# 1-Schematic_tiny_bloom.net
KiCad netlist of a schematic drawn in EasyEDA
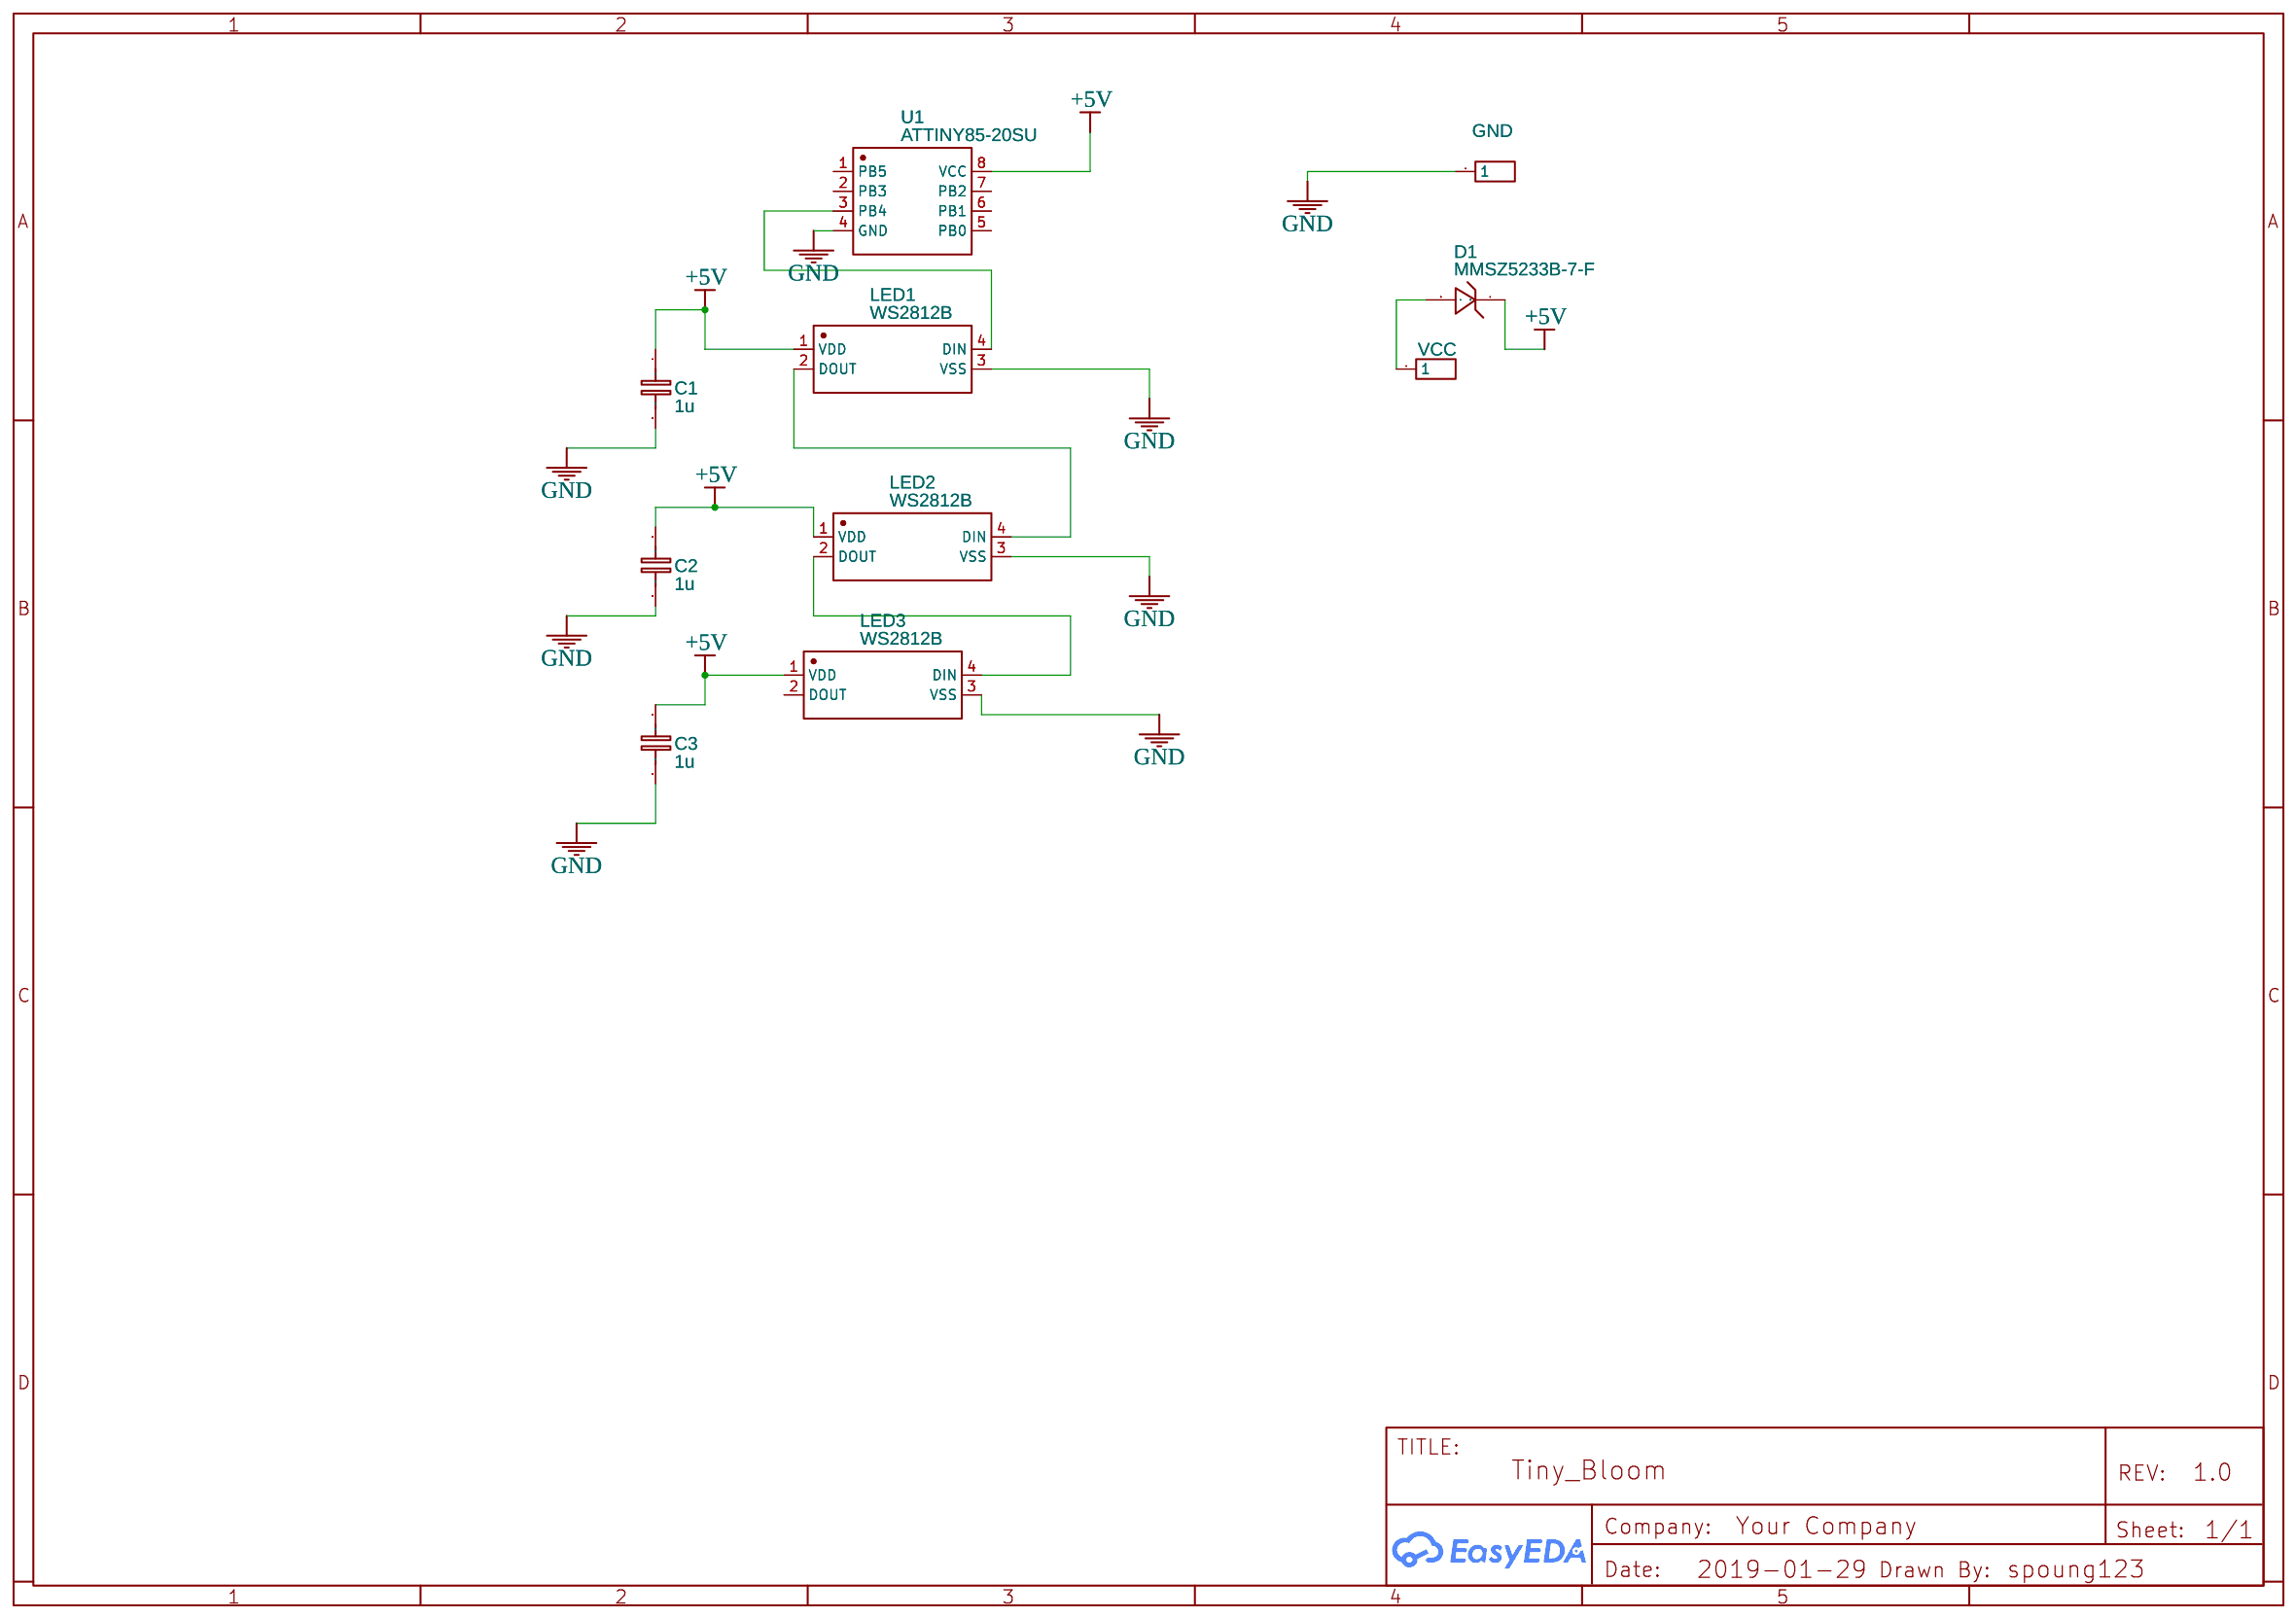
[diagram p0: schematic sheet]

(export (version "E")
  (design (tool "Eeschema 10.0.6"))
  (components
    (comp (ref "C1")
      (value "1u")
      (fields (field (name "BOM_Manufacturer Part") "?"))
      (libsource (lib "") (part "Cap_0603_EU"))
    )
    (comp (ref "C2")
      (value "1u")
      (fields (field (name "BOM_Manufacturer Part") "?"))
      (libsource (lib "") (part "Cap_0603_EU"))
    )
    (comp (ref "C3")
      (value "1u")
      (fields (field (name "BOM_Manufacturer Part") "?"))
      (libsource (lib "") (part "Cap_0603_EU"))
    )
    (comp (ref "D1")
      (value "MMSZ5233B-7-F")
      (fields (field (name "BOM_Supplier Part") "C151381"))
      (libsource (lib "") (part "Unknown_735_145"))
    )
    (comp (ref "GND")
      (value "Header-Male-2.54_1x1")
      (fields (field (name "BOM_Supplier Part") "C81276"))
      (libsource (lib "") (part "Unknown_745_80"))
    )
    (comp (ref "LED1")
      (value "WS2812B")
      (fields (field (name "BOM_Supplier Part") "C114585"))
      (libsource (lib "") (part "Unknown_445_160"))
    )
    (comp (ref "LED2")
      (value "WS2812B")
      (fields (field (name "BOM_Supplier Part") "C114585"))
      (libsource (lib "") (part "Unknown_455_255"))
    )
    (comp (ref "LED3")
      (value "WS2812B")
      (fields (field (name "BOM_Supplier Part") "C114585"))
      (libsource (lib "") (part "Unknown_440_325"))
    )
    (comp (ref "U1")
      (value "ATTINY85-20SU")
      (fields (field (name "BOM_Supplier Part") "C89852"))
      (libsource (lib "") (part "Unknown_455_95"))
    )
    (comp (ref "VCC")
      (value "Header-Male-2.54_1x1")
      (fields (field (name "BOM_Supplier Part") "C81276"))
      (libsource (lib "") (part "Unknown_715_180"))
    )
  )
  (nets
    (net (code "1") (name "+5V") (class "Default")
      (node (ref "C1") (pin "1") (pinfunction "1_1") (pintype "unspecified"))
      (node (ref "C2") (pin "1") (pinfunction "1_1") (pintype "unspecified"))
      (node (ref "C3") (pin "1") (pinfunction "1_1") (pintype "unspecified"))
      (node (ref "D1") (pin "1") (pinfunction "C_1") (pintype "unspecified"))
      (node (ref "LED1") (pin "1") (pinfunction "VDD_1") (pintype "unspecified"))
      (node (ref "LED2") (pin "1") (pinfunction "VDD_1") (pintype "unspecified"))
      (node (ref "LED3") (pin "1") (pinfunction "VDD_1") (pintype "unspecified"))
      (node (ref "U1") (pin "8") (pinfunction "VCC_8") (pintype "unspecified"))
    )
    (net (code "2") (name "GND") (class "Default")
      (node (ref "C1") (pin "2") (pinfunction "2_2") (pintype "unspecified"))
      (node (ref "C2") (pin "2") (pinfunction "2_2") (pintype "unspecified"))
      (node (ref "C3") (pin "2") (pinfunction "2_2") (pintype "unspecified"))
      (node (ref "GND") (pin "1") (pinfunction "1_1") (pintype "input"))
      (node (ref "LED1") (pin "3") (pinfunction "VSS_3") (pintype "unspecified"))
      (node (ref "LED2") (pin "3") (pinfunction "VSS_3") (pintype "unspecified"))
      (node (ref "LED3") (pin "3") (pinfunction "VSS_3") (pintype "unspecified"))
      (node (ref "U1") (pin "4") (pinfunction "GND_4") (pintype "unspecified"))
    )
    (net (code "3") (name "Net-(D1-A)") (class "Default")
      (node (ref "D1") (pin "2") (pinfunction "A_2") (pintype "unspecified"))
      (node (ref "VCC") (pin "1") (pinfunction "1_1") (pintype "input"))
    )
    (net (code "4") (name "Net-(LED1-DIN)") (class "Default")
      (node (ref "LED1") (pin "4") (pinfunction "DIN_4") (pintype "unspecified"))
      (node (ref "U1") (pin "3") (pinfunction "PB4_3") (pintype "unspecified"))
    )
    (net (code "5") (name "Net-(LED1-DOUT)") (class "Default")
      (node (ref "LED1") (pin "2") (pinfunction "DOUT_2") (pintype "unspecified"))
      (node (ref "LED2") (pin "4") (pinfunction "DIN_4") (pintype "unspecified"))
    )
    (net (code "6") (name "Net-(LED2-DOUT)") (class "Default")
      (node (ref "LED2") (pin "2") (pinfunction "DOUT_2") (pintype "unspecified"))
      (node (ref "LED3") (pin "4") (pinfunction "DIN_4") (pintype "unspecified"))
    )
    (net (code "7") (name "unconnected-(LED3-DOUT-Pad2)") (class "Default")
      (node (ref "LED3") (pin "2") (pinfunction "DOUT_2") (pintype "unspecified"))
    )
    (net (code "8") (name "unconnected-(U1-PB0-Pad5)") (class "Default")
      (node (ref "U1") (pin "5") (pinfunction "PB0_5") (pintype "unspecified"))
    )
    (net (code "9") (name "unconnected-(U1-PB1-Pad6)") (class "Default")
      (node (ref "U1") (pin "6") (pinfunction "PB1_6") (pintype "unspecified"))
    )
    (net (code "10") (name "unconnected-(U1-PB2-Pad7)") (class "Default")
      (node (ref "U1") (pin "7") (pinfunction "PB2_7") (pintype "unspecified"))
    )
    (net (code "11") (name "unconnected-(U1-PB3-Pad2)") (class "Default")
      (node (ref "U1") (pin "2") (pinfunction "PB3_2") (pintype "unspecified"))
    )
    (net (code "12") (name "unconnected-(U1-PB5-Pad1)") (class "Default")
      (node (ref "U1") (pin "1") (pinfunction "PB5_1") (pintype "unspecified"))
    )
  )
)
